# esq.net
KiCad netlist of a schematic drawn in Altium Designer
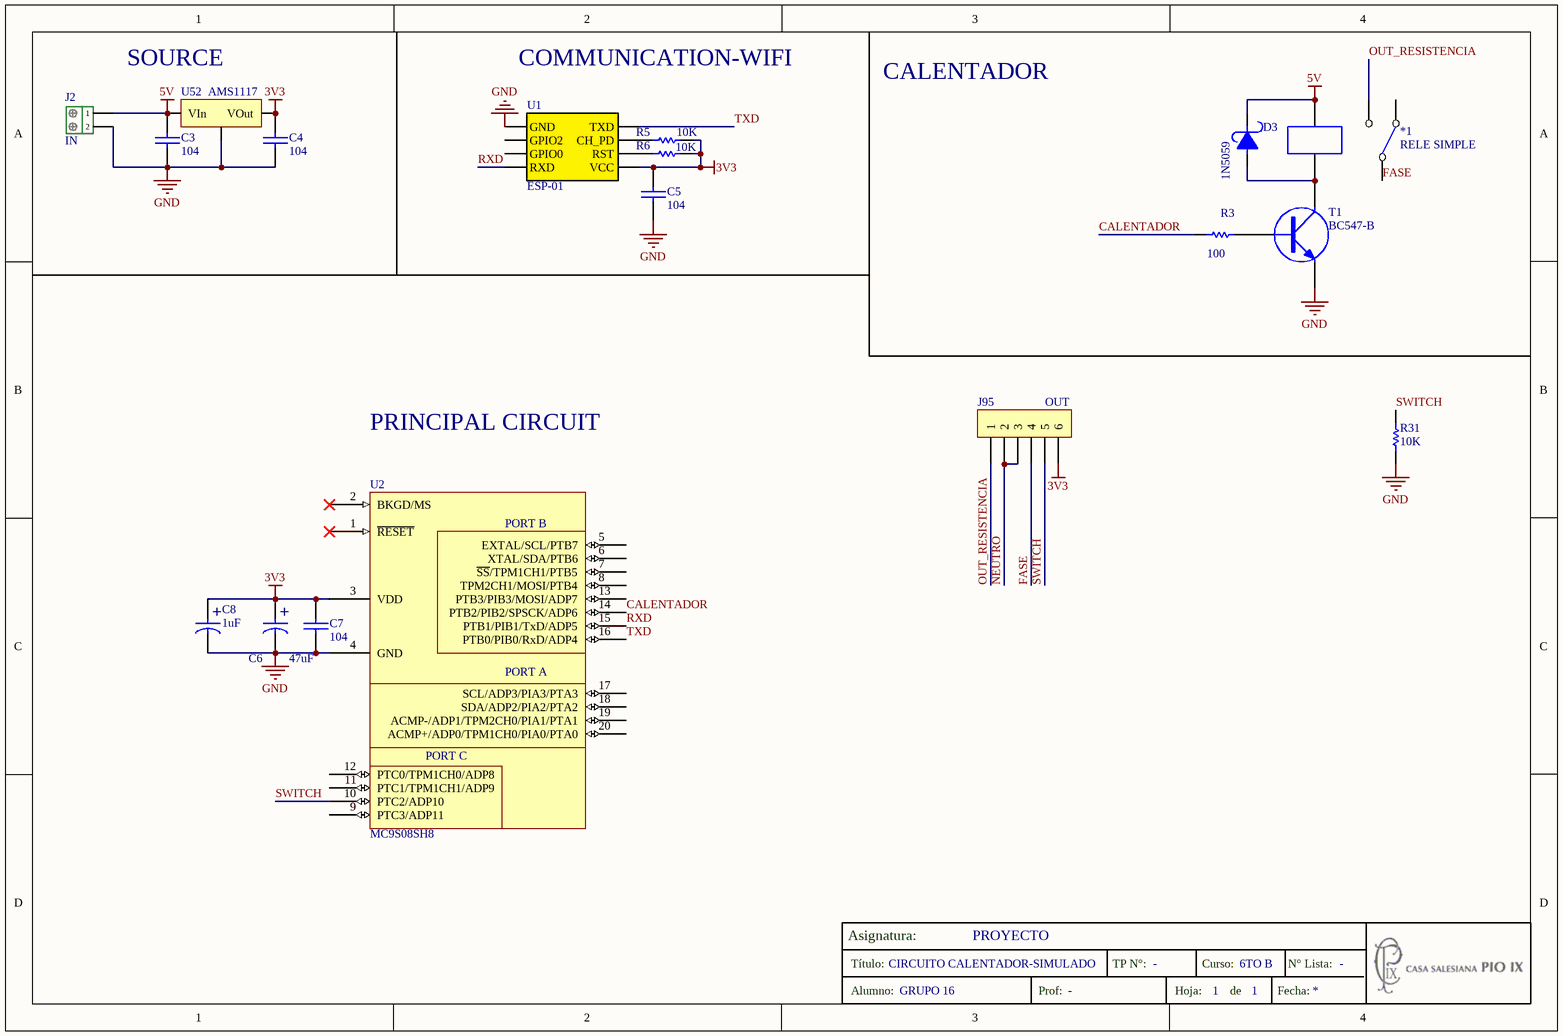
[diagram p0: esq.SchDoc]

(export (version "E")
  (design (tool "Eeschema 10.0.6"))
  (components
    (comp (ref "*1")
      (value "RELE SIMPLE")
      (footprint "RELE SERIE 943")
      (libsource (lib "Schlib") (part "RELE SIMPLE"))
    )
    (comp (ref "C3")
      (value "104")
      (footprint "0805")
      (description "cap")
      (fields (field (name "AUTOR") "Guido Spataro"))
      (libsource (lib "Schlib1") (part "CAP"))
    )
    (comp (ref "C4")
      (value "104")
      (footprint "0805")
      (description "cap")
      (fields (field (name "AUTOR") "Guido Spataro"))
      (libsource (lib "Schlib1") (part "CAP"))
    )
    (comp (ref "C5")
      (value "104")
      (footprint "0805")
      (description "cap")
      (fields (field (name "AUTOR") "Guido Spataro"))
      (libsource (lib "scdlib") (part "CAP"))
    )
    (comp (ref "C6")
      (value "47uF")
      (footprint "CAP100RP")
      (description "Cap polarizado")
      (libsource (lib "Schlib") (part "CAPPOL"))
    )
    (comp (ref "C7")
      (value "104")
      (footprint "0805")
      (description "cap")
      (fields (field (name "AUTOR") "Guido Spataro"))
      (libsource (lib "Schlib1") (part "CAP"))
    )
    (comp (ref "C8")
      (value "1uF")
      (footprint "CAP100RP")
      (description "Cap polarizado")
      (libsource (lib "Schlib") (part "CAPPOL"))
    )
    (comp (ref "D3")
      (value "1N5059")
      (footprint "Diodo")
      (description "Diodo")
      (fields (field (name "AUTOR") "Guido Spataro"))
      (libsource (lib "Schlib1") (part "DIODO SCHOTTKY"))
    )
    (comp (ref "J2")
      (value "IN")
      (footprint "BORNERA2")
      (description "Bornera de 2 pines")
      (fields (field (name "AUTOR") "Guido Spataro"))
      (libsource (lib "Schlib1") (part "Bornera_2"))
    )
    (comp (ref "J95") (value "OUT") (footprint "BORNERA6") (libsource (lib "Schlib") (part "BORNERA 6")))
    (comp (ref "R3")
      (value "100")
      (footprint "0805")
      (description "Resistencia")
      (fields (field (name "AUTOR") "Guido Spataro"))
      (libsource (lib "Schlib1") (part "RES"))
    )
    (comp (ref "R5")
      (value "10K")
      (footprint "0805")
      (description "Resistencia")
      (fields (field (name "AUTOR") "Guido Spataro"))
      (libsource (lib "scdlib") (part "RES"))
    )
    (comp (ref "R6")
      (value "10K")
      (footprint "0805")
      (description "Resistencia")
      (fields (field (name "AUTOR") "Guido Spataro"))
      (libsource (lib "scdlib") (part "RES"))
    )
    (comp (ref "R31")
      (value "10K")
      (footprint "0805")
      (description "Resistencia")
      (fields (field (name "AUTOR") "Guido Spataro"))
      (libsource (lib "Schlib1") (part "RES"))
    )
    (comp (ref "T1")
      (value "BC547-B")
      (footprint "SOT23")
      (libsource (lib "Schlib1") (part "TRANSISTOR NPN"))
    )
    (comp (ref "U1") (value "ESP-01") (footprint "ESP-01") (libsource (lib "Schlib") (part "ESP-01")))
    (comp (ref "U2")
      (value "MC9S08SH8")
      (footprint "SH8")
      (description "Micro controlador")
      (fields (field (name "AUTOR") "Guido Spataro"))
      (libsource (lib "Schlib1") (part "MC9S08SH8"))
    )
    (comp (ref "U52") (value "AMS1117") (footprint "AMS1117") (libsource (lib "Schlib") (part "AMS1117")))
  )
  (nets
    (net (code "1") (name "/CALENTADOR") (class "Default")
      (node (ref "R3") (pin "2") (pinfunction "2_2") (pintype "passive"))
      (node (ref "U2") (pin "14") (pinfunction "PTB2/PIB2/SPSCK/ADP6_14") (pintype "bidirectional"))
    )
    (net (code "2") (name "/FASE") (class "Default")
      (node (ref "*1") (pin "C1") (pinfunction "C1_C1") (pintype "passive"))
      (node (ref "J95") (pin "4") (pinfunction "4_4") (pintype "passive"))
    )
    (net (code "3") (name "/NEUTRO") (class "Default")
      (node (ref "J95") (pin "2") (pinfunction "2_2") (pintype "passive"))
      (node (ref "J95") (pin "3") (pinfunction "3_3") (pintype "passive"))
    )
    (net (code "4") (name "/OUT_RESISTENCIA") (class "Default")
      (node (ref "*1") (pin "NA1") (pinfunction "NA1_NA1") (pintype "passive"))
      (node (ref "J95") (pin "1") (pinfunction "1_1") (pintype "passive"))
    )
    (net (code "5") (name "/RXD") (class "Default")
      (node (ref "U1") (pin "4") (pinfunction "RXD_4") (pintype "passive"))
      (node (ref "U2") (pin "15") (pinfunction "PTB1/PIB1/TxD/ADP5_15") (pintype "bidirectional"))
    )
    (net (code "6") (name "/SWITCH") (class "Default")
      (node (ref "J95") (pin "5") (pinfunction "5_5") (pintype "passive"))
      (node (ref "R31") (pin "1") (pinfunction "1_1") (pintype "passive"))
      (node (ref "U2") (pin "10") (pinfunction "PTC2/ADP10_10") (pintype "bidirectional"))
    )
    (net (code "7") (name "/TXD") (class "Default")
      (node (ref "U1") (pin "5") (pinfunction "TXD_5") (pintype "passive"))
      (node (ref "U2") (pin "16") (pinfunction "PTB0/PIB0/RxD/ADP4_16") (pintype "bidirectional"))
    )
    (net (code "8") (name "3V3") (class "Default")
      (node (ref "C4") (pin "1") (pinfunction "1_1") (pintype "passive"))
      (node (ref "C5") (pin "2") (pinfunction "2_2") (pintype "passive"))
      (node (ref "C6") (pin "1") (pinfunction "1_1") (pintype "passive"))
      (node (ref "C7") (pin "1") (pinfunction "1_1") (pintype "passive"))
      (node (ref "C8") (pin "1") (pinfunction "1_1") (pintype "passive"))
      (node (ref "J95") (pin "6") (pinfunction "6_6") (pintype "passive"))
      (node (ref "R5") (pin "1") (pinfunction "1_1") (pintype "passive"))
      (node (ref "R6") (pin "1") (pinfunction "1_1") (pintype "passive"))
      (node (ref "U1") (pin "8") (pinfunction "VCC_8") (pintype "passive"))
      (node (ref "U2") (pin "3") (pinfunction "VDD_3") (pintype "passive"))
      (node (ref "U52") (pin "3") (pinfunction "VOut_3") (pintype "passive"))
    )
    (net (code "9") (name "5V") (class "Default")
      (node (ref "*1") (pin "B1") (pinfunction "B1_B1") (pintype "passive"))
      (node (ref "C3") (pin "1") (pinfunction "1_1") (pintype "passive"))
      (node (ref "D3") (pin "2") (pinfunction "2_2") (pintype "passive"))
      (node (ref "J2") (pin "1") (pinfunction "1_1") (pintype "passive"))
      (node (ref "U52") (pin "1") (pinfunction "VIn_1") (pintype "passive"))
    )
    (net (code "10") (name "GND") (class "Default")
      (node (ref "C3") (pin "2") (pinfunction "2_2") (pintype "passive"))
      (node (ref "C4") (pin "2") (pinfunction "2_2") (pintype "passive"))
      (node (ref "C5") (pin "1") (pinfunction "1_1") (pintype "passive"))
      (node (ref "C6") (pin "2") (pinfunction "2_2") (pintype "passive"))
      (node (ref "C7") (pin "2") (pinfunction "2_2") (pintype "passive"))
      (node (ref "C8") (pin "2") (pinfunction "2_2") (pintype "passive"))
      (node (ref "J2") (pin "2") (pinfunction "2_2") (pintype "passive"))
      (node (ref "R31") (pin "2") (pinfunction "2_2") (pintype "passive"))
      (node (ref "T1") (pin "3") (pinfunction "E_3") (pintype "passive"))
      (node (ref "U1") (pin "1") (pinfunction "GND_1") (pintype "passive"))
      (node (ref "U2") (pin "4") (pinfunction "GND_4") (pintype "passive"))
      (node (ref "U52") (pin "2") (pinfunction "GND_2") (pintype "passive"))
    )
    (net (code "11") (name "Net-(T1-B)") (class "Default")
      (node (ref "R3") (pin "1") (pinfunction "1_1") (pintype "passive"))
      (node (ref "T1") (pin "1") (pinfunction "B_1") (pintype "passive"))
    )
    (net (code "12") (name "Net-(T1-C)") (class "Default")
      (node (ref "*1") (pin "B2") (pinfunction "B2_B2") (pintype "passive"))
      (node (ref "D3") (pin "1") (pinfunction "1_1") (pintype "passive"))
      (node (ref "T1") (pin "2") (pinfunction "C_2") (pintype "passive"))
    )
    (net (code "13") (name "Net-(U1-CH_PD)") (class "Default")
      (node (ref "R5") (pin "2") (pinfunction "2_2") (pintype "passive"))
      (node (ref "U1") (pin "6") (pinfunction "CH_PD_6") (pintype "passive"))
    )
    (net (code "14") (name "Net-(U1-RST)") (class "Default")
      (node (ref "R6") (pin "2") (pinfunction "2_2") (pintype "passive"))
      (node (ref "U1") (pin "7") (pinfunction "RST_7") (pintype "passive"))
    )
    (net (code "15") (name "unconnected-(*1-PadNC1)") (class "Default")
      (node (ref "*1") (pin "NC1") (pinfunction "NC1_NC1") (pintype "passive"))
    )
    (net (code "16") (name "unconnected-(U1-GPIO0-Pad3)") (class "Default")
      (node (ref "U1") (pin "3") (pinfunction "GPIO0_3") (pintype "passive"))
    )
    (net (code "17") (name "unconnected-(U1-GPIO2-Pad2)") (class "Default")
      (node (ref "U1") (pin "2") (pinfunction "GPIO2_2") (pintype "passive"))
    )
    (net (code "18") (name "unconnected-(U2-ACMP+{slash}ADP0{slash}TPM1CH0{slash}PIA0{slash}PTA0-Pad20)") (class "Default")
      (node (ref "U2") (pin "20") (pinfunction "ACMP+/ADP0/TPM1CH0/PIA0/PTA0_20") (pintype "bidirectional"))
    )
    (net (code "19") (name "unconnected-(U2-ACMP-{slash}ADP1{slash}TPM2CH0{slash}PIA1{slash}PTA1-Pad19)") (class "Default")
      (node (ref "U2") (pin "19") (pinfunction "ACMP-/ADP1/TPM2CH0/PIA1/PTA1_19") (pintype "bidirectional"))
    )
    (net (code "20") (name "unconnected-(U2-BKGD{slash}MS-Pad2)") (class "Default")
      (node (ref "U2") (pin "2") (pinfunction "BKGD/MS_2") (pintype "input+no_connect"))
    )
    (net (code "21") (name "unconnected-(U2-EXTAL{slash}SCL{slash}PTB7-Pad5)") (class "Default")
      (node (ref "U2") (pin "5") (pinfunction "EXTAL/SCL/PTB7_5") (pintype "bidirectional"))
    )
    (net (code "22") (name "unconnected-(U2-PTB3{slash}PIB3{slash}MOSI{slash}ADP7-Pad13)") (class "Default")
      (node (ref "U2") (pin "13") (pinfunction "PTB3/PIB3/MOSI/ADP7_13") (pintype "bidirectional"))
    )
    (net (code "23") (name "unconnected-(U2-PTC0{slash}TPM1CH0{slash}ADP8-Pad12)") (class "Default")
      (node (ref "U2") (pin "12") (pinfunction "PTC0/TPM1CH0/ADP8_12") (pintype "bidirectional"))
    )
    (net (code "24") (name "unconnected-(U2-PTC1{slash}TPM1CH1{slash}ADP9-Pad11)") (class "Default")
      (node (ref "U2") (pin "11") (pinfunction "PTC1/TPM1CH1/ADP9_11") (pintype "bidirectional"))
    )
    (net (code "25") (name "unconnected-(U2-PTC3{slash}ADP11-Pad9)") (class "Default")
      (node (ref "U2") (pin "9") (pinfunction "PTC3/ADP11_9") (pintype "bidirectional"))
    )
    (net (code "26") (name "unconnected-(U2-SCL{slash}ADP3{slash}PIA3{slash}PTA3-Pad17)") (class "Default")
      (node (ref "U2") (pin "17") (pinfunction "SCL/ADP3/PIA3/PTA3_17") (pintype "bidirectional"))
    )
    (net (code "27") (name "unconnected-(U2-SDA{slash}ADP2{slash}PIA2{slash}PTA2-Pad18)") (class "Default")
      (node (ref "U2") (pin "18") (pinfunction "SDA/ADP2/PIA2/PTA2_18") (pintype "bidirectional"))
    )
    (net (code "28") (name "unconnected-(U2-TPM2CH1{slash}MOSI{slash}PTB4-Pad8)") (class "Default")
      (node (ref "U2") (pin "8") (pinfunction "TPM2CH1/MOSI/PTB4_8") (pintype "bidirectional"))
    )
    (net (code "29") (name "unconnected-(U2-XTAL{slash}SDA{slash}PTB6-Pad6)") (class "Default")
      (node (ref "U2") (pin "6") (pinfunction "XTAL/SDA/PTB6_6") (pintype "bidirectional"))
    )
    (net (code "30") (name "unconnected-(U2-~{RESET}-Pad1)") (class "Default")
      (node (ref "U2") (pin "1") (pinfunction "~{RESET}_1") (pintype "input+no_connect"))
    )
    (net (code "31") (name "unconnected-(U2-~{SS}{slash}TPM1CH1{slash}PTB5-Pad7)") (class "Default")
      (node (ref "U2") (pin "7") (pinfunction "~{SS}/TPM1CH1/PTB5_7") (pintype "bidirectional"))
    )
  )
)
